# IM-EG2-Top-Board.net
KiCad netlist of a schematic drawn in EAGLE
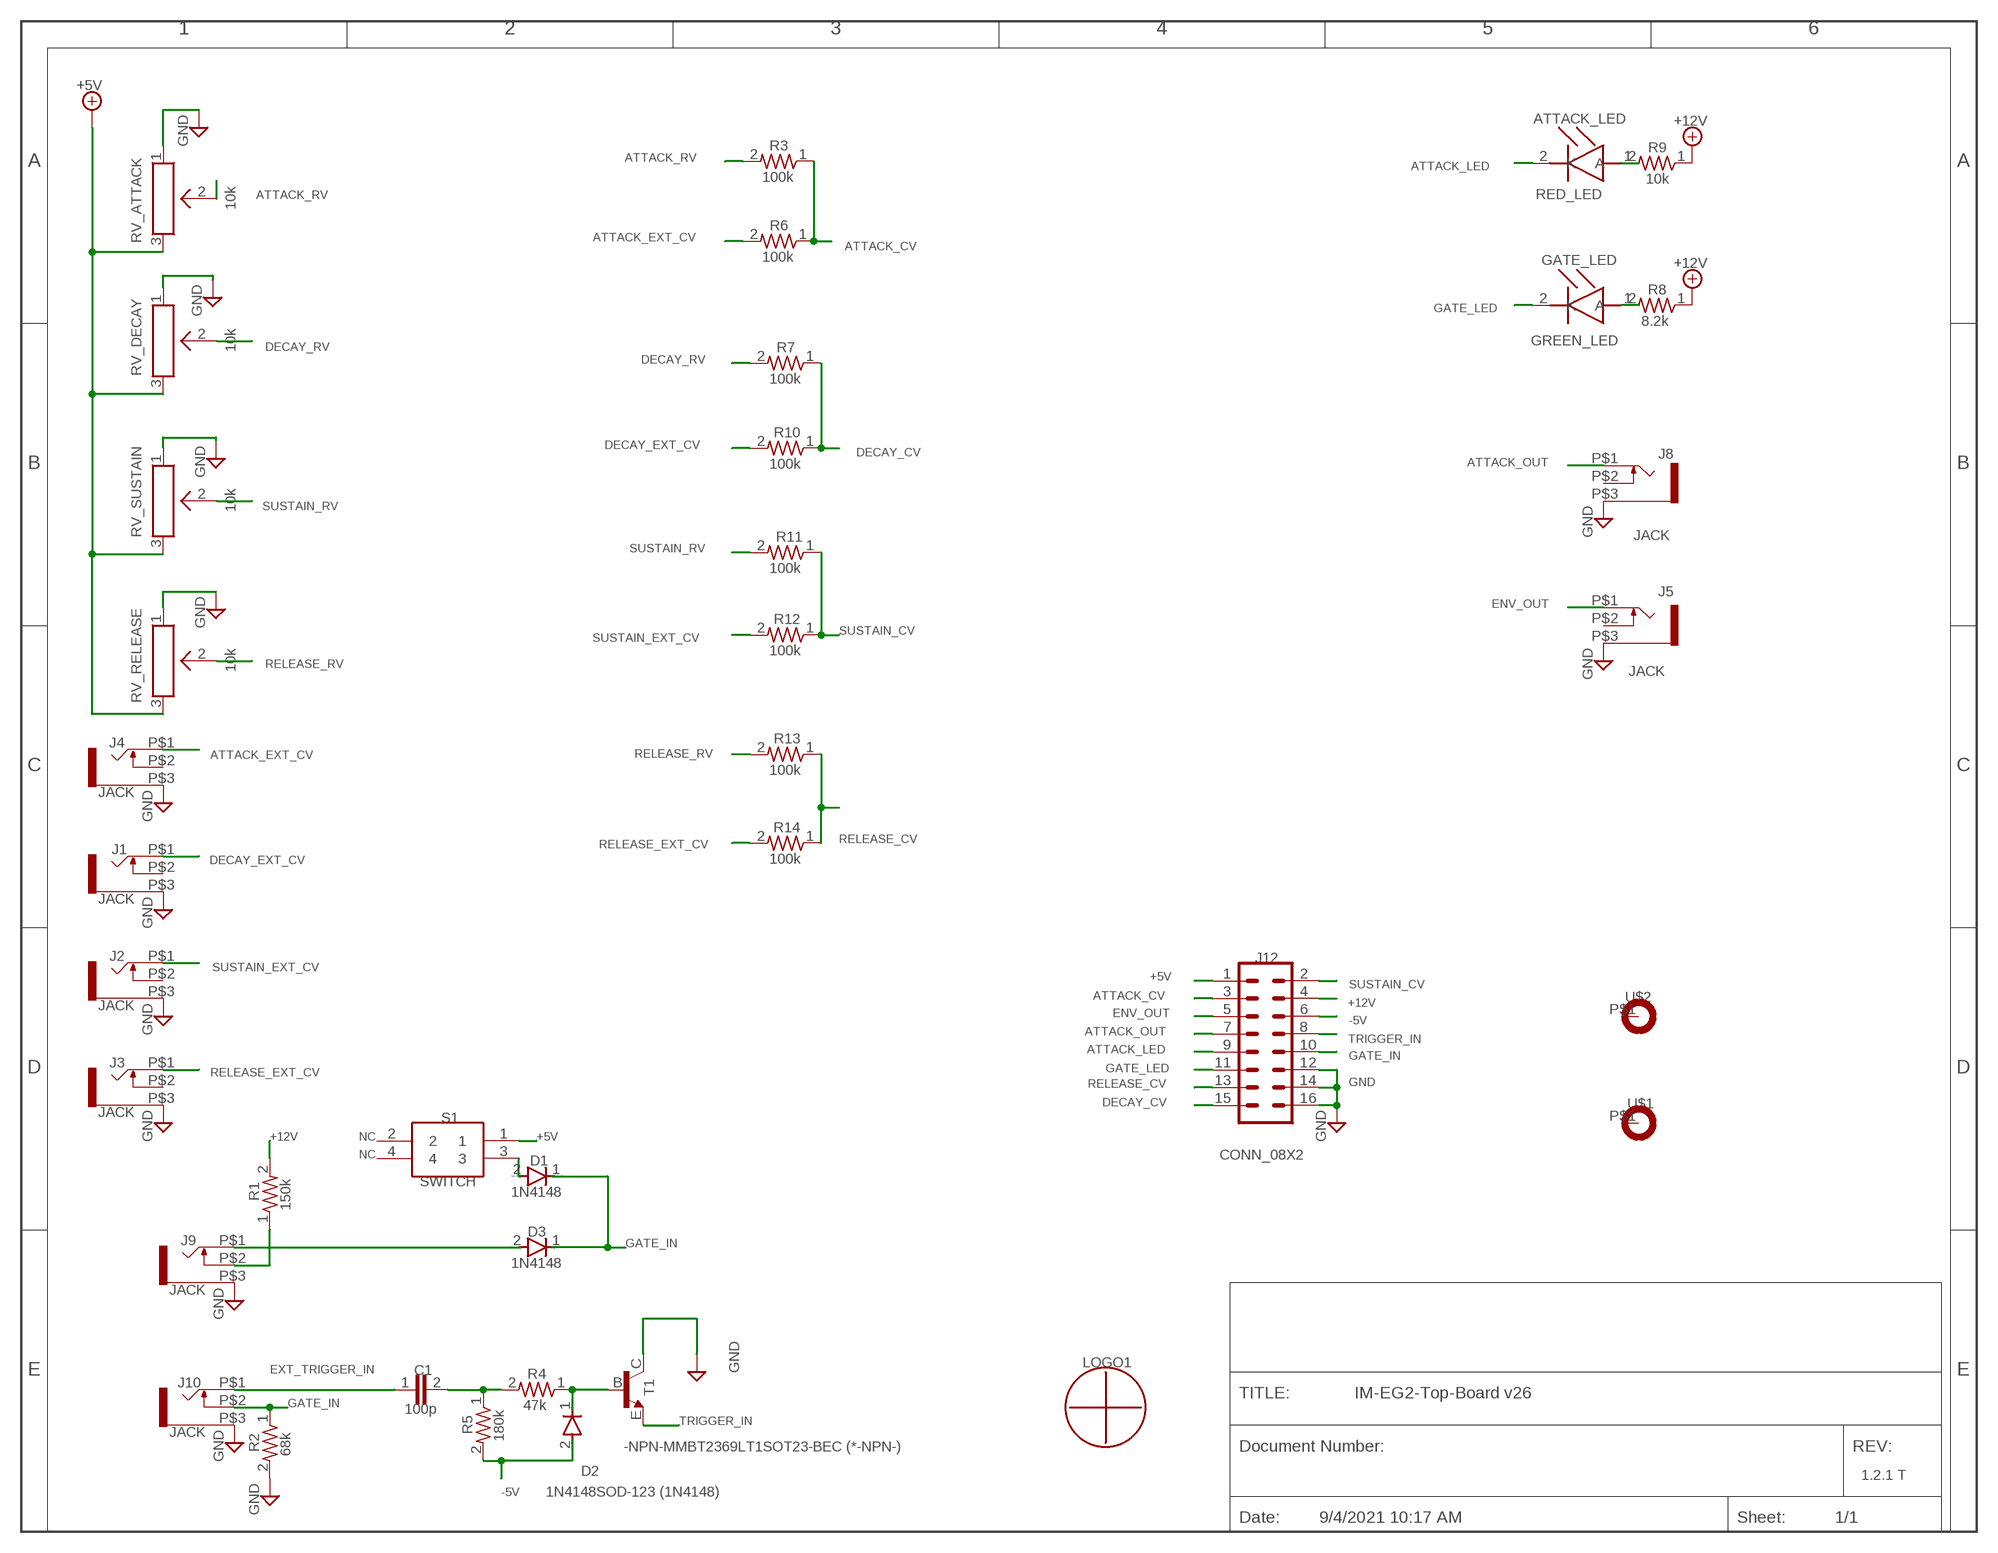
[diagram p0: schematic, sheet 1]

(export (version "E")
  (design (tool "Eeschema 10.0.6"))
  (components
    (comp (ref "ATTACK_LED")
      (value "RED_LED")
      (footprint "eagle-import:LEDRD254W60D320H440B")
      (libsource (lib "eagle-import") (part "TLHG4405TLHG4405-3MM_(TLHG4405)"))
    )
    (comp (ref "C1")
      (value "100p")
      (footprint "eagle-import:C0805")
      (libsource (lib "eagle-import") (part "C-EUC0805_(C-EU)"))
    )
    (comp (ref "D1")
      (value "1N4148")
      (footprint "eagle-import:SOD3715X135")
      (libsource (lib "eagle-import") (part "1N4148SOD-123_(1N4148)"))
    )
    (comp (ref "D2")
      (value "1N4148SOD-123_(1N4148)")
      (footprint "eagle-import:SOD3715X135")
      (libsource (lib "eagle-import") (part "1N4148SOD-123_(1N4148)"))
    )
    (comp (ref "D3")
      (value "1N4148")
      (footprint "eagle-import:SOD3715X135")
      (libsource (lib "eagle-import") (part "1N4148SOD-123_(1N4148)"))
    )
    (comp (ref "GATE_LED")
      (value "GREEN_LED")
      (footprint "eagle-import:LEDRD254W60D320H440B")
      (libsource (lib "eagle-import") (part "TLHG4405TLHG4405-3MM_(TLHG4405)"))
    )
    (comp (ref "J1")
      (value "JACK")
      (footprint "eagle-import:WQP-PJ301M-12_JACK")
      (libsource (lib "eagle-import") (part "WQP-PJ301M-12_JACK"))
    )
    (comp (ref "J2")
      (value "JACK")
      (footprint "eagle-import:WQP-PJ301M-12_JACK")
      (libsource (lib "eagle-import") (part "WQP-PJ301M-12_JACK"))
    )
    (comp (ref "J3")
      (value "JACK")
      (footprint "eagle-import:WQP-PJ301M-12_JACK")
      (libsource (lib "eagle-import") (part "WQP-PJ301M-12_JACK"))
    )
    (comp (ref "J4")
      (value "JACK")
      (footprint "eagle-import:WQP-PJ301M-12_JACK")
      (libsource (lib "eagle-import") (part "WQP-PJ301M-12_JACK"))
    )
    (comp (ref "J5")
      (value "JACK")
      (footprint "eagle-import:WQP-PJ301M-12_JACK")
      (libsource (lib "eagle-import") (part "WQP-PJ301M-12_JACK_4"))
    )
    (comp (ref "J8")
      (value "JACK")
      (footprint "eagle-import:WQP-PJ301M-12_JACK")
      (libsource (lib "eagle-import") (part "WQP-PJ301M-12_JACK_4"))
    )
    (comp (ref "J9")
      (value "JACK")
      (footprint "eagle-import:WQP-PJ301M-12_JACK")
      (libsource (lib "eagle-import") (part "WQP-PJ301M-12_JACK"))
    )
    (comp (ref "J10")
      (value "JACK")
      (footprint "eagle-import:WQP-PJ301M-12_JACK")
      (libsource (lib "eagle-import") (part "WQP-PJ301M-12_JACK"))
    )
    (comp (ref "J12")
      (value "CONN_08X2")
      (footprint "eagle-import:2X8")
      (libsource (lib "eagle-import") (part "CONN_08X2"))
    )
    (comp (ref "LOGO1")
      (value "IM-LOGO-4MM-1M")
      (footprint "eagle-import:IM-LOGO-4MM-1M")
      (libsource (lib "eagle-import") (part "IM-LOGO-4MM-1M"))
    )
    (comp (ref "R1")
      (value "150k")
      (footprint "eagle-import:R0805")
      (libsource (lib "eagle-import") (part "R-US_R0805_(R-US_)"))
    )
    (comp (ref "R2")
      (value "68k")
      (footprint "eagle-import:R0805")
      (libsource (lib "eagle-import") (part "R-US_R0805_(R-US_)"))
    )
    (comp (ref "R3")
      (value "100k")
      (footprint "eagle-import:R0805")
      (libsource (lib "eagle-import") (part "R-US_R0805_(R-US_)"))
    )
    (comp (ref "R4")
      (value "47k")
      (footprint "eagle-import:R0805")
      (libsource (lib "eagle-import") (part "R-US_R0805_(R-US_)"))
    )
    (comp (ref "R5")
      (value "180k")
      (footprint "eagle-import:R0805")
      (libsource (lib "eagle-import") (part "R-US_R0805_(R-US_)"))
    )
    (comp (ref "R6")
      (value "100k")
      (footprint "eagle-import:R0805")
      (libsource (lib "eagle-import") (part "R-US_R0805_(R-US_)"))
    )
    (comp (ref "R7")
      (value "100k")
      (footprint "eagle-import:R0805")
      (libsource (lib "eagle-import") (part "R-US_R0805_(R-US_)"))
    )
    (comp (ref "R8")
      (value "8.2k")
      (footprint "eagle-import:R0805")
      (libsource (lib "eagle-import") (part "R-US_R0805_(R-US_)"))
    )
    (comp (ref "R9")
      (value "10k")
      (footprint "eagle-import:R0805")
      (libsource (lib "eagle-import") (part "R-US_R0805_(R-US_)"))
    )
    (comp (ref "R10")
      (value "100k")
      (footprint "eagle-import:R0805")
      (libsource (lib "eagle-import") (part "R-US_R0805_(R-US_)"))
    )
    (comp (ref "R11")
      (value "100k")
      (footprint "eagle-import:R0805")
      (libsource (lib "eagle-import") (part "R-US_R0805_(R-US_)"))
    )
    (comp (ref "R12")
      (value "100k")
      (footprint "eagle-import:R0805")
      (libsource (lib "eagle-import") (part "R-US_R0805_(R-US_)"))
    )
    (comp (ref "R13")
      (value "100k")
      (footprint "eagle-import:R0805")
      (libsource (lib "eagle-import") (part "R-US_R0805_(R-US_)"))
    )
    (comp (ref "R14")
      (value "100k")
      (footprint "eagle-import:R0805")
      (libsource (lib "eagle-import") (part "R-US_R0805_(R-US_)"))
    )
    (comp (ref "RV_ATTACK")
      (value "10k")
      (footprint "eagle-import:RD901F4015R1B100K00DL1")
      (fields
        (field (name "MANUFACTURER_PART_NUMBER") "RD901F-40-15R1-B100K-00DL1")
        (field (name "MOUSER_PART_NUMBER") "311-1940F-15R1-B100K")
      )
      (libsource (lib "eagle-import") (part "ALPHA-RD901F-40-15R"))
    )
    (comp (ref "RV_DECAY")
      (value "10k")
      (footprint "eagle-import:RD901F4015R1B100K00DL1")
      (fields
        (field (name "MANUFACTURER_PART_NUMBER") "RD901F-40-15R1-B100K-00DL1")
        (field (name "MOUSER_PART_NUMBER") "311-1940F-15R1-B100K")
      )
      (libsource (lib "eagle-import") (part "ALPHA-RD901F-40-15R"))
    )
    (comp (ref "RV_RELEASE")
      (value "10k")
      (footprint "eagle-import:RD901F4015R1B100K00DL1")
      (fields
        (field (name "MANUFACTURER_PART_NUMBER") "RD901F-40-15R1-B100K-00DL1")
        (field (name "MOUSER_PART_NUMBER") "311-1940F-15R1-B100K")
      )
      (libsource (lib "eagle-import") (part "ALPHA-RD901F-40-15R"))
    )
    (comp (ref "RV_SUSTAIN")
      (value "10k")
      (footprint "eagle-import:RD901F4015R1B100K00DL1")
      (fields
        (field (name "MANUFACTURER_PART_NUMBER") "RD901F-40-15R1-B100K-00DL1")
        (field (name "MOUSER_PART_NUMBER") "311-1940F-15R1-B100K")
      )
      (libsource (lib "eagle-import") (part "ALPHA-RD901F-40-15R"))
    )
    (comp (ref "S1")
      (value "SWITCH")
      (footprint "eagle-import:SKHHDHA010")
      (fields
        (field (name "MANUFACTURER_PART_NUMBER") "SKHHDUA010")
        (field (name "MOUSER_PART_NUMBER") "688-SKHHDU")
      )
      (libsource (lib "eagle-import") (part "SKHHDUA010"))
    )
    (comp (ref "T1")
      (value "-NPN-MMBT2369LT1SOT23-BEC_(-NPN-)")
      (footprint "eagle-import:SOT23-BEC")
      (libsource (lib "eagle-import") (part "-NPN-MMBT2369LT1SOT23-BEC_(-NPN-)"))
    )
    (comp (ref "U$1")
      (value "MOUNT-HOLE-EURORACK3.4-HOLE_(MOUNT-HOLE-EURORACK)")
      (footprint "eagle-import:MOUNT-HOLE-EURORACK")
      (libsource (lib "eagle-import") (part "MOUNT-HOLE-EURORACK3.4-HOLE_(MOUNT-HOLE-EURORACK)"))
    )
    (comp (ref "U$2")
      (value "MOUNT-HOLE-EURORACK3.4-HOLE_(MOUNT-HOLE-EURORACK)")
      (footprint "eagle-import:MOUNT-HOLE-EURORACK")
      (libsource (lib "eagle-import") (part "MOUNT-HOLE-EURORACK3.4-HOLE_(MOUNT-HOLE-EURORACK)"))
    )
  )
  (nets
    (net (code "1") (name "+5V") (class "Default")
      (node (ref "J12") (pin "1") (pinfunction "1_1") (pintype "passive"))
      (node (ref "RV_ATTACK") (pin "3") (pinfunction "3_3") (pintype "bidirectional"))
      (node (ref "RV_DECAY") (pin "3") (pinfunction "3_3") (pintype "bidirectional"))
      (node (ref "RV_RELEASE") (pin "3") (pinfunction "3_3") (pintype "bidirectional"))
      (node (ref "RV_SUSTAIN") (pin "3") (pinfunction "3_3") (pintype "bidirectional"))
      (node (ref "S1") (pin "1") (pinfunction "1_1") (pintype "bidirectional"))
    )
    (net (code "2") (name "+12V") (class "Default")
      (node (ref "J12") (pin "4") (pinfunction "4_4") (pintype "passive"))
      (node (ref "R1") (pin "2") (pinfunction "2_2") (pintype "passive"))
      (node (ref "R8") (pin "1") (pinfunction "1_1") (pintype "passive"))
      (node (ref "R9") (pin "1") (pinfunction "1_1") (pintype "passive"))
    )
    (net (code "3") (name "/-5V") (class "Default")
      (node (ref "D2") (pin "2") (pinfunction "A_2") (pintype "passive"))
      (node (ref "J12") (pin "6") (pinfunction "6_6") (pintype "passive"))
      (node (ref "R5") (pin "2") (pinfunction "2_2") (pintype "passive"))
    )
    (net (code "4") (name "/ATTACK_CV") (class "Default")
      (node (ref "J12") (pin "3") (pinfunction "3_3") (pintype "passive"))
      (node (ref "R3") (pin "1") (pinfunction "1_1") (pintype "passive"))
      (node (ref "R6") (pin "1") (pinfunction "1_1") (pintype "passive"))
    )
    (net (code "5") (name "/ATTACK_EXT_CV") (class "Default")
      (node (ref "J4") (pin "P$1") (pinfunction "2_P$1") (pintype "passive"))
      (node (ref "R6") (pin "2") (pinfunction "2_2") (pintype "passive"))
    )
    (net (code "6") (name "/ATTACK_LED") (class "Default")
      (node (ref "ATTACK_LED") (pin "2") (pinfunction "K_2") (pintype "bidirectional"))
      (node (ref "J12") (pin "9") (pinfunction "9_9") (pintype "passive"))
    )
    (net (code "7") (name "/ATTACK_OUT") (class "Default")
      (node (ref "J12") (pin "7") (pinfunction "7_7") (pintype "passive"))
      (node (ref "J8") (pin "P$1") (pinfunction "2_P$1") (pintype "passive"))
    )
    (net (code "8") (name "/ATTACK_RV") (class "Default")
      (node (ref "R3") (pin "2") (pinfunction "2_2") (pintype "passive"))
      (node (ref "RV_ATTACK") (pin "2") (pinfunction "2_2") (pintype "bidirectional"))
    )
    (net (code "9") (name "/DECAY_CV") (class "Default")
      (node (ref "J12") (pin "15") (pinfunction "15_15") (pintype "passive"))
      (node (ref "R10") (pin "1") (pinfunction "1_1") (pintype "passive"))
      (node (ref "R7") (pin "1") (pinfunction "1_1") (pintype "passive"))
    )
    (net (code "10") (name "/DECAY_EXT_CV") (class "Default")
      (node (ref "J1") (pin "P$1") (pinfunction "2_P$1") (pintype "passive"))
      (node (ref "R10") (pin "2") (pinfunction "2_2") (pintype "passive"))
    )
    (net (code "11") (name "/DECAY_RV") (class "Default")
      (node (ref "R7") (pin "2") (pinfunction "2_2") (pintype "passive"))
      (node (ref "RV_DECAY") (pin "2") (pinfunction "2_2") (pintype "bidirectional"))
    )
    (net (code "12") (name "/ENV_OUT") (class "Default")
      (node (ref "J12") (pin "5") (pinfunction "5_5") (pintype "passive"))
      (node (ref "J5") (pin "P$1") (pinfunction "2_P$1") (pintype "passive"))
    )
    (net (code "13") (name "/GATE_IN") (class "Default")
      (node (ref "D1") (pin "1") (pinfunction "C_1") (pintype "passive"))
      (node (ref "D3") (pin "1") (pinfunction "C_1") (pintype "passive"))
      (node (ref "J10") (pin "P$2") (pinfunction "3_P$2") (pintype "passive"))
      (node (ref "J12") (pin "10") (pinfunction "10_10") (pintype "passive"))
      (node (ref "R2") (pin "1") (pinfunction "1_1") (pintype "passive"))
    )
    (net (code "14") (name "/GATE_LED") (class "Default")
      (node (ref "GATE_LED") (pin "2") (pinfunction "K_2") (pintype "bidirectional"))
      (node (ref "J12") (pin "11") (pinfunction "11_11") (pintype "passive"))
    )
    (net (code "15") (name "/RELEASE_CV") (class "Default")
      (node (ref "J12") (pin "13") (pinfunction "13_13") (pintype "passive"))
      (node (ref "R13") (pin "1") (pinfunction "1_1") (pintype "passive"))
      (node (ref "R14") (pin "1") (pinfunction "1_1") (pintype "passive"))
    )
    (net (code "16") (name "/RELEASE_EXT_CV") (class "Default")
      (node (ref "J3") (pin "P$1") (pinfunction "2_P$1") (pintype "passive"))
      (node (ref "R14") (pin "2") (pinfunction "2_2") (pintype "passive"))
    )
    (net (code "17") (name "/RELEASE_RV") (class "Default")
      (node (ref "R13") (pin "2") (pinfunction "2_2") (pintype "passive"))
      (node (ref "RV_RELEASE") (pin "2") (pinfunction "2_2") (pintype "bidirectional"))
    )
    (net (code "18") (name "/SUSTAIN_CV") (class "Default")
      (node (ref "J12") (pin "2") (pinfunction "2_2") (pintype "passive"))
      (node (ref "R11") (pin "1") (pinfunction "1_1") (pintype "passive"))
      (node (ref "R12") (pin "1") (pinfunction "1_1") (pintype "passive"))
    )
    (net (code "19") (name "/SUSTAIN_EXT_CV") (class "Default")
      (node (ref "J2") (pin "P$1") (pinfunction "2_P$1") (pintype "passive"))
      (node (ref "R12") (pin "2") (pinfunction "2_2") (pintype "passive"))
    )
    (net (code "20") (name "/SUSTAIN_RV") (class "Default")
      (node (ref "R11") (pin "2") (pinfunction "2_2") (pintype "passive"))
      (node (ref "RV_SUSTAIN") (pin "2") (pinfunction "2_2") (pintype "bidirectional"))
    )
    (net (code "21") (name "/TRIGGER_IN") (class "Default")
      (node (ref "J12") (pin "8") (pinfunction "8_8") (pintype "passive"))
      (node (ref "T1") (pin "E") (pinfunction "E_E") (pintype "passive"))
    )
    (net (code "22") (name "GND") (class "Default")
      (node (ref "J1") (pin "P$3") (pinfunction "1_P$3") (pintype "passive"))
      (node (ref "J10") (pin "P$3") (pinfunction "1_P$3") (pintype "passive"))
      (node (ref "J12") (pin "12") (pinfunction "12_12") (pintype "passive"))
      (node (ref "J12") (pin "14") (pinfunction "14_14") (pintype "passive"))
      (node (ref "J12") (pin "16") (pinfunction "16_16") (pintype "passive"))
      (node (ref "J2") (pin "P$3") (pinfunction "1_P$3") (pintype "passive"))
      (node (ref "J3") (pin "P$3") (pinfunction "1_P$3") (pintype "passive"))
      (node (ref "J4") (pin "P$3") (pinfunction "1_P$3") (pintype "passive"))
      (node (ref "J5") (pin "P$3") (pinfunction "1_P$3") (pintype "passive"))
      (node (ref "J8") (pin "P$3") (pinfunction "1_P$3") (pintype "passive"))
      (node (ref "J9") (pin "P$3") (pinfunction "1_P$3") (pintype "passive"))
      (node (ref "R2") (pin "2") (pinfunction "2_2") (pintype "passive"))
      (node (ref "RV_ATTACK") (pin "1") (pinfunction "1_1") (pintype "bidirectional"))
      (node (ref "RV_DECAY") (pin "1") (pinfunction "1_1") (pintype "bidirectional"))
      (node (ref "RV_RELEASE") (pin "1") (pinfunction "1_1") (pintype "bidirectional"))
      (node (ref "RV_SUSTAIN") (pin "1") (pinfunction "1_1") (pintype "bidirectional"))
      (node (ref "T1") (pin "C") (pinfunction "C_C") (pintype "passive"))
    )
    (net (code "23") (name "Net-(ATTACK_LED-A)") (class "Default")
      (node (ref "ATTACK_LED") (pin "1") (pinfunction "A_1") (pintype "bidirectional"))
      (node (ref "R9") (pin "2") (pinfunction "2_2") (pintype "passive"))
    )
    (net (code "24") (name "Net-(C1-Pad2)") (class "Default")
      (node (ref "C1") (pin "2") (pinfunction "2_2") (pintype "passive"))
      (node (ref "R4") (pin "2") (pinfunction "2_2") (pintype "passive"))
      (node (ref "R5") (pin "1") (pinfunction "1_1") (pintype "passive"))
    )
    (net (code "25") (name "Net-(D1-A)") (class "Default")
      (node (ref "D1") (pin "2") (pinfunction "A_2") (pintype "passive"))
      (node (ref "S1") (pin "3") (pinfunction "3_3") (pintype "bidirectional"))
    )
    (net (code "26") (name "Net-(D2-C)") (class "Default")
      (node (ref "D2") (pin "1") (pinfunction "C_1") (pintype "passive"))
      (node (ref "R4") (pin "1") (pinfunction "1_1") (pintype "passive"))
      (node (ref "T1") (pin "B") (pinfunction "B_B") (pintype "passive"))
    )
    (net (code "27") (name "Net-(D3-A)") (class "Default")
      (node (ref "D3") (pin "2") (pinfunction "A_2") (pintype "passive"))
      (node (ref "J9") (pin "P$1") (pinfunction "2_P$1") (pintype "passive"))
    )
    (net (code "28") (name "Net-(GATE_LED-A)") (class "Default")
      (node (ref "GATE_LED") (pin "1") (pinfunction "A_1") (pintype "bidirectional"))
      (node (ref "R8") (pin "2") (pinfunction "2_2") (pintype "passive"))
    )
    (net (code "29") (name "Net-(J9-3)") (class "Default")
      (node (ref "J9") (pin "P$2") (pinfunction "3_P$2") (pintype "passive"))
      (node (ref "R1") (pin "1") (pinfunction "1_1") (pintype "passive"))
    )
    (net (code "30") (name "Net-(J10-2)") (class "Default")
      (node (ref "C1") (pin "1") (pinfunction "1_1") (pintype "passive"))
      (node (ref "J10") (pin "P$1") (pinfunction "2_P$1") (pintype "passive"))
    )
    (net (code "31") (name "unconnected-(J1-3-PadP$2)") (class "Default")
      (node (ref "J1") (pin "P$2") (pinfunction "3_P$2") (pintype "passive"))
    )
    (net (code "32") (name "unconnected-(J2-3-PadP$2)") (class "Default")
      (node (ref "J2") (pin "P$2") (pinfunction "3_P$2") (pintype "passive"))
    )
    (net (code "33") (name "unconnected-(J3-3-PadP$2)") (class "Default")
      (node (ref "J3") (pin "P$2") (pinfunction "3_P$2") (pintype "passive"))
    )
    (net (code "34") (name "unconnected-(J4-3-PadP$2)") (class "Default")
      (node (ref "J4") (pin "P$2") (pinfunction "3_P$2") (pintype "passive"))
    )
    (net (code "35") (name "unconnected-(J5-3-PadP$2)") (class "Default")
      (node (ref "J5") (pin "P$2") (pinfunction "3_P$2") (pintype "passive"))
    )
    (net (code "36") (name "unconnected-(J8-3-PadP$2)") (class "Default")
      (node (ref "J8") (pin "P$2") (pinfunction "3_P$2") (pintype "passive"))
    )
    (net (code "37") (name "unconnected-(S1-Pad2)") (class "Default")
      (node (ref "S1") (pin "2") (pinfunction "2_2") (pintype "bidirectional"))
    )
    (net (code "38") (name "unconnected-(S1-Pad4)") (class "Default")
      (node (ref "S1") (pin "4") (pinfunction "4_4") (pintype "bidirectional"))
    )
    (net (code "39") (name "unconnected-(U$1-MOUNT-PadP$1)") (class "Default")
      (node (ref "U$1") (pin "P$1") (pinfunction "MOUNT_P$1") (pintype "passive"))
    )
    (net (code "40") (name "unconnected-(U$2-MOUNT-PadP$1)") (class "Default")
      (node (ref "U$2") (pin "P$1") (pinfunction "MOUNT_P$1") (pintype "passive"))
    )
  )
)
